# Schematic_circuit.net
KiCad netlist of a schematic drawn in EAGLE
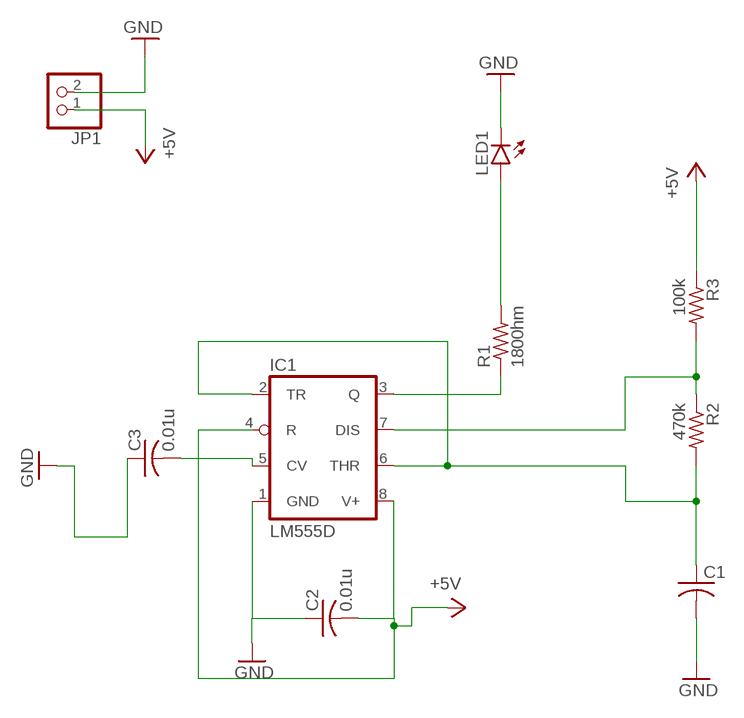
[diagram p0: schematic, sheet 1]

(export (version "E")
  (design (tool "Eeschema 10.0.6"))
  (components
    (comp (ref "C1")
      (value "C-USC0805")
      (footprint "eagle-import:C0805")
      (libsource (lib "eagle-import") (part "C-USC0805"))
    )
    (comp (ref "C2")
      (value "0.01u")
      (footprint "eagle-import:C0805")
      (libsource (lib "eagle-import") (part "C-USC0805"))
    )
    (comp (ref "C3")
      (value "0.01u")
      (footprint "eagle-import:C0805")
      (libsource (lib "eagle-import") (part "C-USC0805"))
    )
    (comp (ref "IC1")
      (value "LM555D")
      (footprint "eagle-import:SO08")
      (libsource (lib "eagle-import") (part "555DLM"))
    )
    (comp (ref "JP1")
      (value "PINHD-1X2")
      (footprint "eagle-import:1X02")
      (libsource (lib "eagle-import") (part "PINHD-1X2"))
    )
    (comp (ref "LED1")
      (value "LED5MM")
      (footprint "eagle-import:LED5MM")
      (libsource (lib "eagle-import") (part "LED5MM"))
    )
    (comp (ref "R1")
      (value "1800hm")
      (footprint "eagle-import:R0805")
      (libsource (lib "eagle-import") (part "R-US_R0805"))
    )
    (comp (ref "R2")
      (value "470k")
      (footprint "eagle-import:R0805")
      (libsource (lib "eagle-import") (part "R-US_R0805"))
    )
    (comp (ref "R3")
      (value "100k")
      (footprint "eagle-import:R0805")
      (libsource (lib "eagle-import") (part "R-US_R0805"))
    )
  )
  (nets
    (net (code "1") (name "+5V") (class "Default")
      (node (ref "C2") (pin "2") (pinfunction "2_2") (pintype "passive"))
      (node (ref "IC1") (pin "4") (pinfunction "R_4") (pintype "input"))
      (node (ref "IC1") (pin "8") (pinfunction "V+_8") (pintype "power_in"))
      (node (ref "JP1") (pin "1") (pinfunction "1_1") (pintype "passive"))
      (node (ref "R3") (pin "1") (pinfunction "1_1") (pintype "passive"))
    )
    (net (code "2") (name "GND") (class "Default")
      (node (ref "C1") (pin "2") (pinfunction "2_2") (pintype "passive"))
      (node (ref "C2") (pin "1") (pinfunction "1_1") (pintype "passive"))
      (node (ref "C3") (pin "1") (pinfunction "1_1") (pintype "passive"))
      (node (ref "IC1") (pin "1") (pinfunction "GND_1") (pintype "power_in"))
      (node (ref "JP1") (pin "2") (pinfunction "2_2") (pintype "passive"))
      (node (ref "LED1") (pin "K") (pinfunction "C_K") (pintype "passive"))
    )
    (net (code "3") (name "Net-(IC1-CV)") (class "Default")
      (node (ref "C3") (pin "2") (pinfunction "2_2") (pintype "passive"))
      (node (ref "IC1") (pin "5") (pinfunction "CV_5") (pintype "input"))
    )
    (net (code "4") (name "Net-(IC1-DIS)") (class "Default")
      (node (ref "IC1") (pin "7") (pinfunction "DIS_7") (pintype "input"))
      (node (ref "R2") (pin "1") (pinfunction "1_1") (pintype "passive"))
      (node (ref "R3") (pin "2") (pinfunction "2_2") (pintype "passive"))
    )
    (net (code "5") (name "Net-(IC1-Q)") (class "Default")
      (node (ref "IC1") (pin "3") (pinfunction "Q_3") (pintype "output"))
      (node (ref "R1") (pin "1") (pinfunction "1_1") (pintype "passive"))
    )
    (net (code "6") (name "Net-(IC1-THR)") (class "Default")
      (node (ref "C1") (pin "1") (pinfunction "1_1") (pintype "passive"))
      (node (ref "IC1") (pin "2") (pinfunction "TR_2") (pintype "input"))
      (node (ref "IC1") (pin "6") (pinfunction "THR_6") (pintype "input"))
      (node (ref "R2") (pin "2") (pinfunction "2_2") (pintype "passive"))
    )
    (net (code "7") (name "Net-(LED1-PadA)") (class "Default")
      (node (ref "LED1") (pin "A") (pinfunction "A_A") (pintype "passive"))
      (node (ref "R1") (pin "2") (pinfunction "2_2") (pintype "passive"))
    )
  )
)
